# MSW_V2.net
KiCad netlist of a schematic drawn in Altium Designer
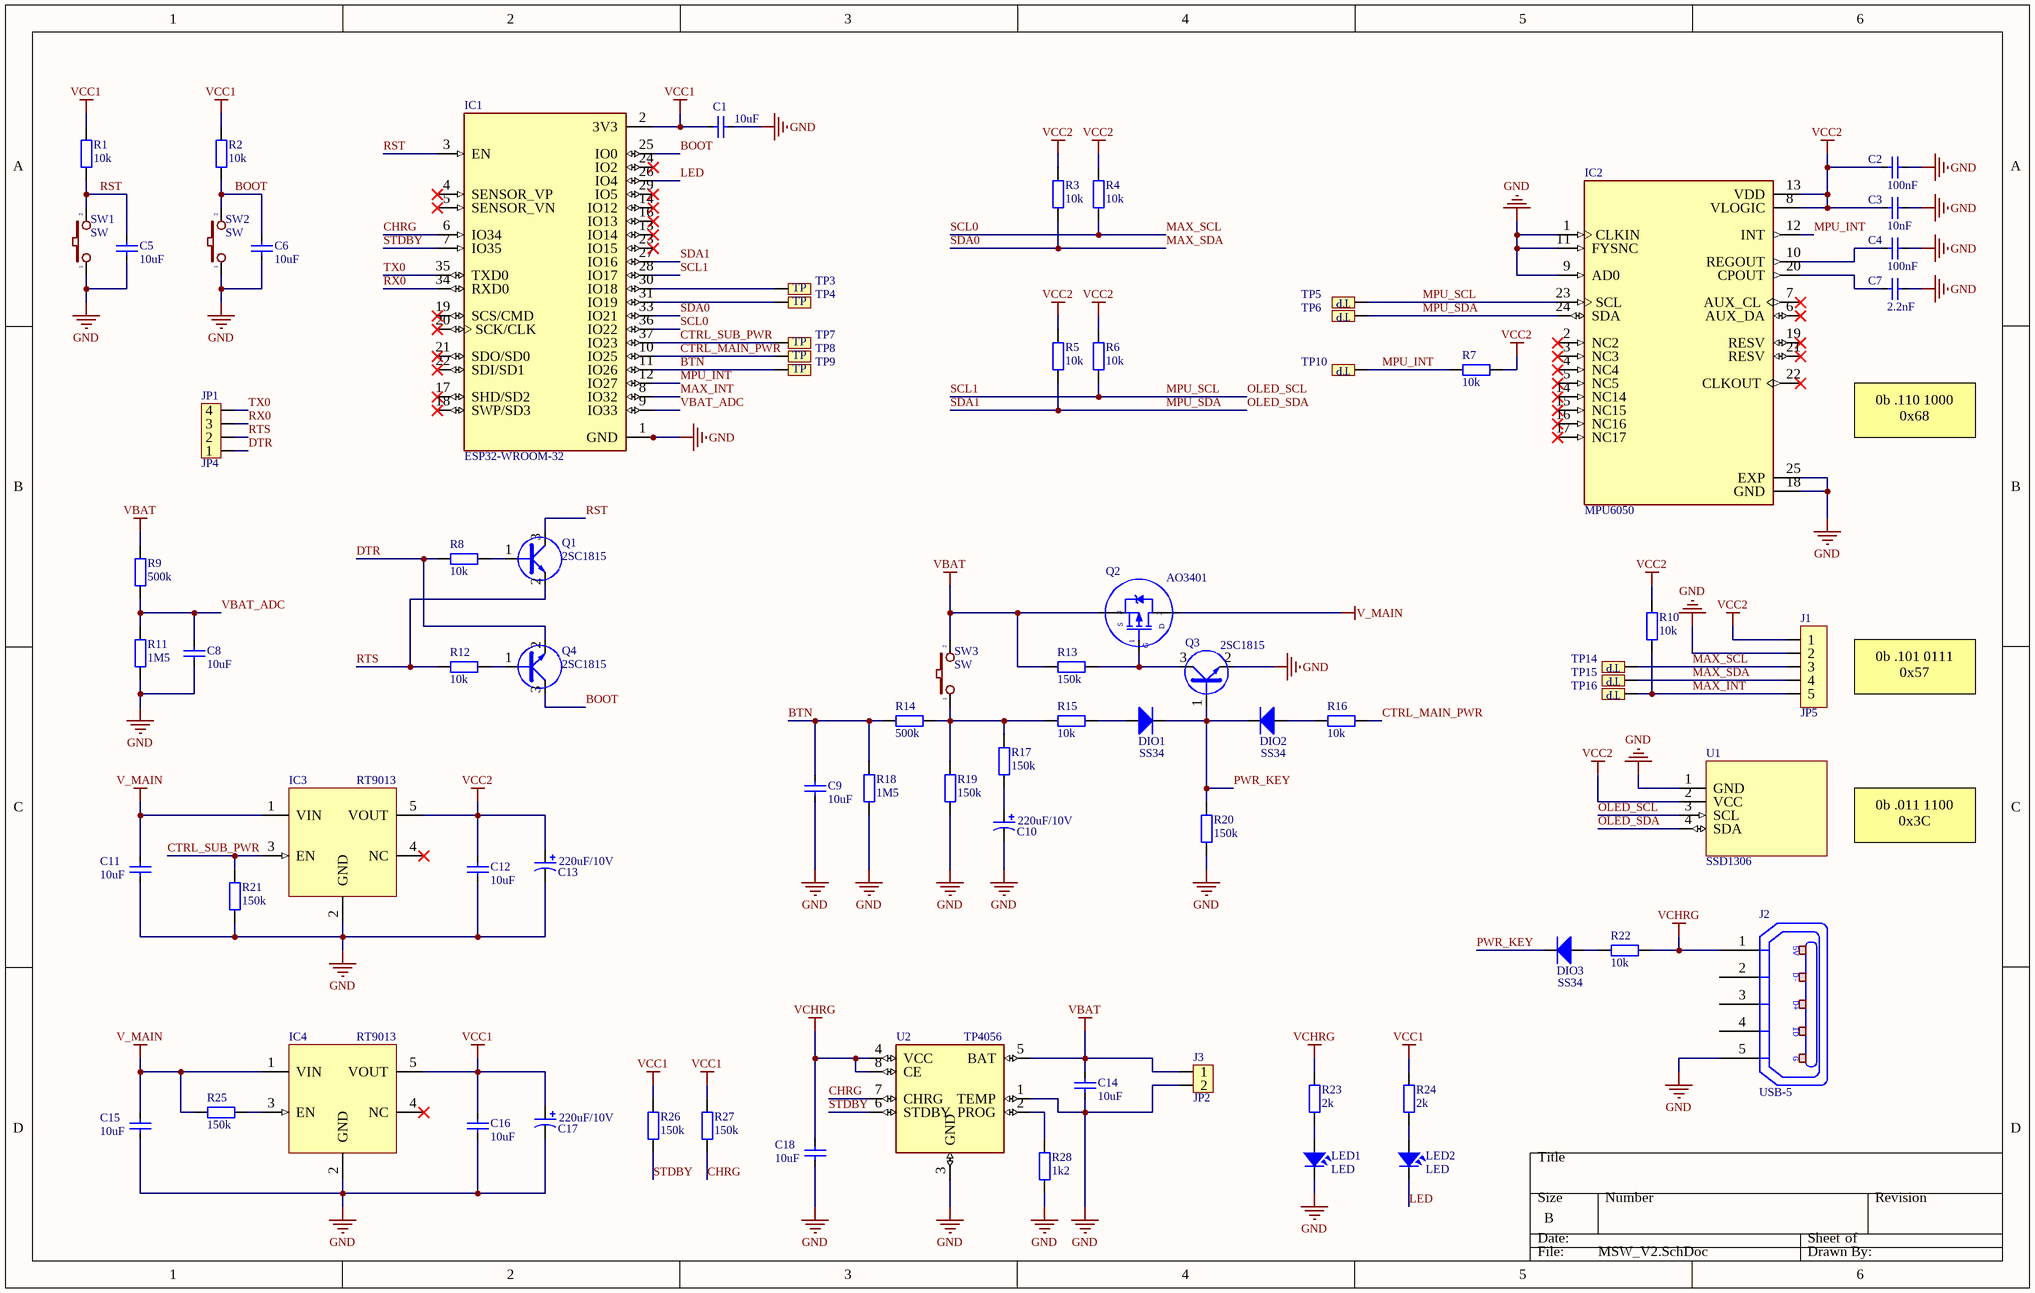
[diagram p0: MSW_V2.SchDoc]

(export (version "E")
  (design (tool "Eeschema 10.0.6"))
  (components
    (comp (ref "C1")
      (value "10uF")
      (footprint "CAP_0603")
      (description "Capacitor")
      (fields (field (name "PUBLISHER") "Altium Limited"))
      (libsource (lib "My Library") (part "CapSMD"))
    )
    (comp (ref "C2")
      (value "100nF")
      (footprint "CAP_0603")
      (description "Capacitor")
      (fields (field (name "PUBLISHER") "Altium Limited"))
      (libsource (lib "My Library") (part "CapSMD"))
    )
    (comp (ref "C3")
      (value "10nF")
      (footprint "CAP_0603")
      (description "Capacitor")
      (fields (field (name "PUBLISHER") "Altium Limited"))
      (libsource (lib "My Library") (part "CapSMD"))
    )
    (comp (ref "C4")
      (value "100nF")
      (footprint "CAP_0603")
      (description "Capacitor")
      (fields (field (name "PUBLISHER") "Altium Limited"))
      (libsource (lib "My Library") (part "CapSMD"))
    )
    (comp (ref "C5")
      (value "10uF")
      (footprint "CAP_0603")
      (description "Capacitor")
      (fields (field (name "PUBLISHER") "Altium Limited"))
      (libsource (lib "My Library") (part "CapSMD"))
    )
    (comp (ref "C6")
      (value "10uF")
      (footprint "CAP_0603")
      (description "Capacitor")
      (fields (field (name "PUBLISHER") "Altium Limited"))
      (libsource (lib "My Library") (part "CapSMD"))
    )
    (comp (ref "C7")
      (value "2.2nF")
      (footprint "CAP_0603")
      (description "Capacitor")
      (fields (field (name "PUBLISHER") "Altium Limited"))
      (libsource (lib "My Library") (part "CapSMD"))
    )
    (comp (ref "C8")
      (value "10uF")
      (footprint "CAP_0603")
      (description "Capacitor")
      (fields (field (name "PUBLISHER") "Altium Limited"))
      (libsource (lib "My Library") (part "CapSMD"))
    )
    (comp (ref "C9")
      (value "10uF")
      (footprint "CAP_0603")
      (description "Capacitor")
      (fields (field (name "PUBLISHER") "Altium Limited"))
      (libsource (lib "My Library") (part "CapSMD"))
    )
    (comp (ref "C10")
      (value "220uF/10V")
      (footprint "CAP_7343")
      (description "Polazied Tantalum Capacitor")
      (libsource (lib "My Library") (part "CAP_TAN_SMD"))
    )
    (comp (ref "C11")
      (value "10uF")
      (footprint "CAP_0603")
      (description "Capacitor")
      (fields (field (name "PUBLISHER") "Altium Limited"))
      (libsource (lib "My Library") (part "CapSMD"))
    )
    (comp (ref "C12")
      (value "10uF")
      (footprint "CAP_0603")
      (description "Capacitor")
      (fields (field (name "PUBLISHER") "Altium Limited"))
      (libsource (lib "My Library") (part "CapSMD"))
    )
    (comp (ref "C13")
      (value "220uF/10V")
      (footprint "CAP_7343")
      (description "Polazied Tantalum Capacitor")
      (libsource (lib "My Library") (part "CAP_TAN_SMD"))
    )
    (comp (ref "C14")
      (value "10uF")
      (footprint "CAP_0603")
      (description "Capacitor")
      (fields (field (name "PUBLISHER") "Altium Limited"))
      (libsource (lib "My Library") (part "CapSMD"))
    )
    (comp (ref "C15")
      (value "10uF")
      (footprint "CAP_0603")
      (description "Capacitor")
      (fields (field (name "PUBLISHER") "Altium Limited"))
      (libsource (lib "My Library") (part "CapSMD"))
    )
    (comp (ref "C16")
      (value "10uF")
      (footprint "CAP_0603")
      (description "Capacitor")
      (fields (field (name "PUBLISHER") "Altium Limited"))
      (libsource (lib "My Library") (part "CapSMD"))
    )
    (comp (ref "C17")
      (value "220uF/10V")
      (footprint "CAP_7343")
      (description "Polazied Tantalum Capacitor")
      (libsource (lib "My Library") (part "CAP_TAN_SMD"))
    )
    (comp (ref "C18")
      (value "10uF")
      (footprint "CAP_0603")
      (description "Capacitor")
      (fields (field (name "PUBLISHER") "Altium Limited"))
      (libsource (lib "My Library") (part "CapSMD"))
    )
    (comp (ref "DIO1")
      (value "SS34")
      (footprint "DIO-214AC(SMA)")
      (description "Default Diode")
      (fields (field (name "PUBLISHER") "Altium Limited"))
      (libsource (lib "My Library") (part "Diode SMD"))
    )
    (comp (ref "DIO2")
      (value "SS34")
      (footprint "DIO-214AC(SMA)")
      (description "Default Diode")
      (fields (field (name "PUBLISHER") "Altium Limited"))
      (libsource (lib "My Library") (part "Diode SMD"))
    )
    (comp (ref "DIO3")
      (value "SS34")
      (footprint "DIO-214AC(SMA)")
      (description "Default Diode")
      (fields (field (name "PUBLISHER") "Altium Limited"))
      (libsource (lib "My Library") (part "Diode SMD"))
    )
    (comp (ref "IC1")
      (value "ESP32-WROOM-32")
      (footprint "MODULE_ESP32-WROOM-32")
      (description "Bluetooth, WiFi Transceiver Module 2.4GHz ~ 2.5GHz Surface Mount")
      (fields (field (name "MF") "Espressif Systems") (field (name "DIGI-KEY_PART_NUMBER") "1904-1010-1-ND"))
      (libsource (lib "My Library") (part "ESP32-WROOM-32"))
    )
    (comp (ref "IC2")
      (value "MPU6050")
      (footprint "QFN24")
      (description "3-axis gyroscope, 3-axis accelerometer")
      (libsource (lib "My Library") (part "MPU6050_Chip"))
    )
    (comp (ref "IC3")
      (value "RT9013")
      (footprint "SOT23-5")
      (description "RT9013-33GB IC REG LINEAR 3.3V 500mA SOT23-5")
      (libsource (lib "My Library") (part "RT9013"))
    )
    (comp (ref "IC4")
      (value "RT9013")
      (footprint "SOT23-5")
      (description "RT9013-33GB IC REG LINEAR 3.3V 500mA SOT23-5")
      (libsource (lib "My Library") (part "RT9013"))
    )
    (comp (ref "J1")
      (value "JP5")
      (footprint "Header5 - TH - 1.25MM")
      (description "WR-PHD 2.54 mm Angled Socket Header")
      (fields
        (field (name "MANUFACTURER") "Würth Elektronik eiSos GmbH")
        (field (name "PARTNO") "613005143121")
        (field (name "CREATED BY") "Karrer Zheng")
      )
      (libsource (lib "My Library") (part "JP5x1"))
    )
    (comp (ref "J2")
      (value "USB-5")
      (footprint "USB-M4")
      (fields
        (field (name "MANUFACTURER") "FCI")
        (field (name "MANUFACTURER PART NUMBER") "10118193-0001LF")
        (field (name ".CREATOR") "MM")
        (field (name ".CHECKED PCB") "RF")
        (field (name ".CHECKED SCH") "MM")
      )
      (libsource (lib "My Library") (part "USB-5"))
    )
    (comp (ref "J3")
      (value "JP2")
      (footprint "JP2-C1T")
      (description "WR-PHD 2.54 mm Angled Socket Header")
      (fields
        (field (name "MANUFACTURER") "Würth Elektronik eiSos GmbH")
        (field (name "PARTNO") "613002143121")
        (field (name "CREATED BY") "Karrer Zheng")
      )
      (libsource (lib "My Library") (part "JP2"))
    )
    (comp (ref "JP1")
      (value "JP4")
      (footprint "Header4 - TH - 1.25MM")
      (description "WR-PHD 2.54 mm Angled Socket Header")
      (fields
        (field (name "MANUFACTURER") "Würth Elektronik eiSos GmbH")
        (field (name "PARTNO") "613004143121")
        (field (name "CREATED BY") "Karrer Zheng")
      )
      (libsource (lib "My Library") (part "JP4"))
    )
    (comp (ref "LED1")
      (value "LED")
      (footprint "LED-0805-Red")
      (description "LED Single colour Green and Red")
      (libsource (lib "My Library") (part "LED"))
    )
    (comp (ref "LED2")
      (value "LED")
      (footprint "LED-0805-Blue")
      (description "LED Single colour Green and Red")
      (libsource (lib "My Library") (part "LED"))
    )
    (comp (ref "Q1")
      (value "2SC1815")
      (footprint "SOT23D")
      (description "NPN 600mW, ECB")
      (libsource (lib "") (part "C1815_2"))
    )
    (comp (ref "Q2")
      (value "AO3401")
      (footprint "SOT23A")
      (description "Generic P Channel MOSFET")
      (libsource (lib "My Library") (part "MOSFET_P"))
    )
    (comp (ref "Q3")
      (value "2SC1815")
      (footprint "SOT23D")
      (description "NPN 600mW, ECB")
      (libsource (lib "My Library") (part "C1815"))
    )
    (comp (ref "Q4")
      (value "2SC1815")
      (footprint "SOT23D")
      (description "NPN 600mW, ECB")
      (libsource (lib "") (part "C1815_1"))
    )
    (comp (ref "R1")
      (value "10k")
      (footprint "RES-SMD-0603")
      (description "Resistor SMD")
      (fields
        (field (name "MANUFACTURER") "Generic Components")
        (field (name "PUBLISHER") "Altium Hobart Technology Centre")
      )
      (libsource (lib "My Library") (part "Resistor - SMD"))
    )
    (comp (ref "R2")
      (value "10k")
      (footprint "RES-SMD-0603")
      (description "Resistor SMD")
      (fields
        (field (name "MANUFACTURER") "Generic Components")
        (field (name "PUBLISHER") "Altium Hobart Technology Centre")
      )
      (libsource (lib "My Library") (part "Resistor - SMD"))
    )
    (comp (ref "R3")
      (value "10k")
      (footprint "RES-SMD-0603")
      (description "Resistor SMD")
      (fields
        (field (name "MANUFACTURER") "Generic Components")
        (field (name "PUBLISHER") "Altium Hobart Technology Centre")
      )
      (libsource (lib "My Library") (part "Resistor - SMD"))
    )
    (comp (ref "R4")
      (value "10k")
      (footprint "RES-SMD-0603")
      (description "Resistor SMD")
      (fields
        (field (name "MANUFACTURER") "Generic Components")
        (field (name "PUBLISHER") "Altium Hobart Technology Centre")
      )
      (libsource (lib "My Library") (part "Resistor - SMD"))
    )
    (comp (ref "R5")
      (value "10k")
      (footprint "RES-SMD-0603")
      (description "Resistor SMD")
      (fields
        (field (name "MANUFACTURER") "Generic Components")
        (field (name "PUBLISHER") "Altium Hobart Technology Centre")
      )
      (libsource (lib "My Library") (part "Resistor - SMD"))
    )
    (comp (ref "R6")
      (value "10k")
      (footprint "RES-SMD-0603")
      (description "Resistor SMD")
      (fields
        (field (name "MANUFACTURER") "Generic Components")
        (field (name "PUBLISHER") "Altium Hobart Technology Centre")
      )
      (libsource (lib "My Library") (part "Resistor - SMD"))
    )
    (comp (ref "R7")
      (value "10k")
      (footprint "RES-SMD-0603")
      (description "Resistor SMD")
      (fields
        (field (name "MANUFACTURER") "Generic Components")
        (field (name "PUBLISHER") "Altium Hobart Technology Centre")
      )
      (libsource (lib "My Library") (part "Resistor - SMD"))
    )
    (comp (ref "R8")
      (value "10k")
      (footprint "RES-SMD-0603")
      (description "Resistor SMD")
      (fields
        (field (name "MANUFACTURER") "Generic Components")
        (field (name "PUBLISHER") "Altium Hobart Technology Centre")
      )
      (libsource (lib "My Library") (part "Resistor - SMD"))
    )
    (comp (ref "R9")
      (value "500k")
      (footprint "RES-SMD-0603")
      (description "Resistor SMD")
      (fields
        (field (name "MANUFACTURER") "Generic Components")
        (field (name "PUBLISHER") "Altium Hobart Technology Centre")
      )
      (libsource (lib "My Library") (part "Resistor - SMD"))
    )
    (comp (ref "R10")
      (value "10k")
      (footprint "RES-SMD-0603")
      (description "Resistor SMD")
      (fields
        (field (name "MANUFACTURER") "Generic Components")
        (field (name "PUBLISHER") "Altium Hobart Technology Centre")
      )
      (libsource (lib "My Library") (part "Resistor - SMD"))
    )
    (comp (ref "R11")
      (value "1M5")
      (footprint "RES-SMD-0603")
      (description "Resistor SMD")
      (fields
        (field (name "MANUFACTURER") "Generic Components")
        (field (name "PUBLISHER") "Altium Hobart Technology Centre")
      )
      (libsource (lib "My Library") (part "Resistor - SMD"))
    )
    (comp (ref "R12")
      (value "10k")
      (footprint "RES-SMD-0603")
      (description "Resistor SMD")
      (fields
        (field (name "MANUFACTURER") "Generic Components")
        (field (name "PUBLISHER") "Altium Hobart Technology Centre")
      )
      (libsource (lib "My Library") (part "Resistor - SMD"))
    )
    (comp (ref "R13")
      (value "150k")
      (footprint "RES-SMD-0603")
      (description "Resistor SMD")
      (fields
        (field (name "MANUFACTURER") "Generic Components")
        (field (name "PUBLISHER") "Altium Hobart Technology Centre")
      )
      (libsource (lib "My Library") (part "Resistor - SMD"))
    )
    (comp (ref "R14")
      (value "500k")
      (footprint "RES-SMD-0603")
      (description "Resistor SMD")
      (fields
        (field (name "MANUFACTURER") "Generic Components")
        (field (name "PUBLISHER") "Altium Hobart Technology Centre")
      )
      (libsource (lib "My Library") (part "Resistor - SMD"))
    )
    (comp (ref "R15")
      (value "10k")
      (footprint "RES-SMD-0603")
      (description "Resistor SMD")
      (fields
        (field (name "MANUFACTURER") "Generic Components")
        (field (name "PUBLISHER") "Altium Hobart Technology Centre")
      )
      (libsource (lib "My Library") (part "Resistor - SMD"))
    )
    (comp (ref "R16")
      (value "10k")
      (footprint "RES-SMD-0603")
      (description "Resistor SMD")
      (fields
        (field (name "MANUFACTURER") "Generic Components")
        (field (name "PUBLISHER") "Altium Hobart Technology Centre")
      )
      (libsource (lib "My Library") (part "Resistor - SMD"))
    )
    (comp (ref "R17")
      (value "150k")
      (footprint "RES-SMD-0603")
      (description "Resistor SMD")
      (fields
        (field (name "MANUFACTURER") "Generic Components")
        (field (name "PUBLISHER") "Altium Hobart Technology Centre")
      )
      (libsource (lib "My Library") (part "Resistor - SMD"))
    )
    (comp (ref "R18")
      (value "1M5")
      (footprint "RES-SMD-0603")
      (description "Resistor SMD")
      (fields
        (field (name "MANUFACTURER") "Generic Components")
        (field (name "PUBLISHER") "Altium Hobart Technology Centre")
      )
      (libsource (lib "My Library") (part "Resistor - SMD"))
    )
    (comp (ref "R19")
      (value "150k")
      (footprint "RES-SMD-0603")
      (description "Resistor SMD")
      (fields
        (field (name "MANUFACTURER") "Generic Components")
        (field (name "PUBLISHER") "Altium Hobart Technology Centre")
      )
      (libsource (lib "My Library") (part "Resistor - SMD"))
    )
    (comp (ref "R20")
      (value "150k")
      (footprint "RES-SMD-0603")
      (description "Resistor SMD")
      (fields
        (field (name "MANUFACTURER") "Generic Components")
        (field (name "PUBLISHER") "Altium Hobart Technology Centre")
      )
      (libsource (lib "My Library") (part "Resistor - SMD"))
    )
    (comp (ref "R21")
      (value "150k")
      (footprint "RES-SMD-0603")
      (description "Resistor SMD")
      (fields
        (field (name "MANUFACTURER") "Generic Components")
        (field (name "PUBLISHER") "Altium Hobart Technology Centre")
      )
      (libsource (lib "My Library") (part "Resistor - SMD"))
    )
    (comp (ref "R22")
      (value "10k")
      (footprint "RES-SMD-0603")
      (description "Resistor SMD")
      (fields
        (field (name "MANUFACTURER") "Generic Components")
        (field (name "PUBLISHER") "Altium Hobart Technology Centre")
      )
      (libsource (lib "My Library") (part "Resistor - SMD"))
    )
    (comp (ref "R23")
      (value "2k")
      (footprint "RES-SMD-0603")
      (description "Resistor SMD")
      (fields
        (field (name "MANUFACTURER") "Generic Components")
        (field (name "PUBLISHER") "Altium Hobart Technology Centre")
      )
      (libsource (lib "My Library") (part "Resistor - SMD"))
    )
    (comp (ref "R24")
      (value "2k")
      (footprint "RES-SMD-0603")
      (description "Resistor SMD")
      (fields
        (field (name "MANUFACTURER") "Generic Components")
        (field (name "PUBLISHER") "Altium Hobart Technology Centre")
      )
      (libsource (lib "My Library") (part "Resistor - SMD"))
    )
    (comp (ref "R25")
      (value "150k")
      (footprint "RES-SMD-0603")
      (description "Resistor SMD")
      (fields
        (field (name "MANUFACTURER") "Generic Components")
        (field (name "PUBLISHER") "Altium Hobart Technology Centre")
      )
      (libsource (lib "My Library") (part "Resistor - SMD"))
    )
    (comp (ref "R26")
      (value "150k")
      (footprint "RES-SMD-0603")
      (description "Resistor SMD")
      (fields
        (field (name "MANUFACTURER") "Generic Components")
        (field (name "PUBLISHER") "Altium Hobart Technology Centre")
      )
      (libsource (lib "My Library") (part "Resistor - SMD"))
    )
    (comp (ref "R27")
      (value "150k")
      (footprint "RES-SMD-0603")
      (description "Resistor SMD")
      (fields
        (field (name "MANUFACTURER") "Generic Components")
        (field (name "PUBLISHER") "Altium Hobart Technology Centre")
      )
      (libsource (lib "My Library") (part "Resistor - SMD"))
    )
    (comp (ref "R28")
      (value "1k2")
      (footprint "RES-SMD-0603")
      (description "Resistor SMD")
      (fields
        (field (name "MANUFACTURER") "Generic Components")
        (field (name "PUBLISHER") "Altium Hobart Technology Centre")
      )
      (libsource (lib "My Library") (part "Resistor - SMD"))
    )
    (comp (ref "SW1")
      (value "SW")
      (footprint "SW 3x2x4")
      (description "Switch button 2 pin")
      (libsource (lib "My Library") (part "SW2"))
    )
    (comp (ref "SW2")
      (value "SW")
      (footprint "SW 3x2x4")
      (description "Switch button 2 pin")
      (libsource (lib "My Library") (part "SW2"))
    )
    (comp (ref "SW3")
      (value "SW")
      (footprint "BUTTON 2P SMD SIDE 2x4x3.5")
      (description "Switch button 2 pin")
      (libsource (lib "My Library") (part "SW2"))
    )
    (comp (ref "TP3")
      (value "TP")
      (footprint "TP_SMD")
      (description "CONNECT 1")
      (libsource (lib "My Library") (part "TP"))
    )
    (comp (ref "TP4")
      (value "TP")
      (footprint "TP_SMD")
      (description "CONNECT 1")
      (libsource (lib "My Library") (part "TP"))
    )
    (comp (ref "TP5")
      (value "TP")
      (footprint "TP_SMD")
      (description "CONNECT 1")
      (libsource (lib "") (part "TP_1"))
    )
    (comp (ref "TP6")
      (value "TP")
      (footprint "TP_SMD")
      (description "CONNECT 1")
      (libsource (lib "") (part "TP_1"))
    )
    (comp (ref "TP7")
      (value "TP")
      (footprint "TP_SMD")
      (description "CONNECT 1")
      (libsource (lib "My Library") (part "TP"))
    )
    (comp (ref "TP8")
      (value "TP")
      (footprint "TP_SMD")
      (description "CONNECT 1")
      (libsource (lib "My Library") (part "TP"))
    )
    (comp (ref "TP9")
      (value "TP")
      (footprint "TP_SMD")
      (description "CONNECT 1")
      (libsource (lib "My Library") (part "TP"))
    )
    (comp (ref "TP10")
      (value "TP")
      (footprint "TP_SMD")
      (description "CONNECT 1")
      (libsource (lib "") (part "TP_1"))
    )
    (comp (ref "TP14")
      (value "TP")
      (footprint "TP_SMD")
      (description "CONNECT 1")
      (libsource (lib "") (part "TP_1"))
    )
    (comp (ref "TP15")
      (value "TP")
      (footprint "TP_SMD")
      (description "CONNECT 1")
      (libsource (lib "") (part "TP_1"))
    )
    (comp (ref "TP16")
      (value "TP")
      (footprint "TP_SMD")
      (description "CONNECT 1")
      (libsource (lib "") (part "TP_1"))
    )
    (comp (ref "U1")
      (value "SSD1306")
      (footprint "OLED 1.3 SSD1306 NON POLE")
      (description "OLED Display 1.3\" SSD1306")
      (libsource (lib "My Library") (part "OLED 1.3 SSD1306"))
    )
    (comp (ref "U2")
      (value "TP4056")
      (footprint "TP4056")
      (description "Complete single cell Li-Ion battery with a constant current / constant voltage linear charger")
      (libsource (lib "My Library") (part "TP4056"))
    )
  )
  (nets
    (net (code "1") (name "/BOOT") (class "Default")
      (node (ref "C6") (pin "2") (pinfunction "2_2") (pintype "passive"))
      (node (ref "IC1") (pin "25") (pinfunction "IO0_25") (pintype "bidirectional"))
      (node (ref "Q4") (pin "3") (pinfunction "C_3") (pintype "passive"))
      (node (ref "R2") (pin "2") (pinfunction "2_2") (pintype "passive"))
      (node (ref "SW2") (pin "2") (pinfunction "2_2") (pintype "passive"))
    )
    (net (code "2") (name "/BTN") (class "Default")
      (node (ref "C9") (pin "2") (pinfunction "2_2") (pintype "passive"))
      (node (ref "IC1") (pin "11") (pinfunction "IO26_11") (pintype "bidirectional"))
      (node (ref "R14") (pin "2") (pinfunction "2_2") (pintype "passive"))
      (node (ref "R18") (pin "2") (pinfunction "2_2") (pintype "passive"))
      (node (ref "TP9") (pin "1") (pinfunction "0_1") (pintype "passive"))
    )
    (net (code "3") (name "/CHRG") (class "Default")
      (node (ref "IC1") (pin "6") (pinfunction "IO34_6") (pintype "input"))
      (node (ref "R27") (pin "2") (pinfunction "2_2") (pintype "passive"))
      (node (ref "U2") (pin "7") (pinfunction "CHRG_7") (pintype "bidirectional"))
    )
    (net (code "4") (name "/CTRL_MAIN_PWR") (class "Default")
      (node (ref "IC1") (pin "10") (pinfunction "IO25_10") (pintype "bidirectional"))
      (node (ref "R16") (pin "2") (pinfunction "2_2") (pintype "passive"))
      (node (ref "TP8") (pin "1") (pinfunction "0_1") (pintype "passive"))
    )
    (net (code "5") (name "/CTRL_SUB_PWR") (class "Default")
      (node (ref "IC1") (pin "37") (pinfunction "IO23_37") (pintype "bidirectional"))
      (node (ref "IC3") (pin "3") (pinfunction "EN_3") (pintype "input"))
      (node (ref "R21") (pin "1") (pinfunction "1_1") (pintype "passive"))
      (node (ref "TP7") (pin "1") (pinfunction "0_1") (pintype "passive"))
    )
    (net (code "6") (name "/DTR") (class "Default")
      (node (ref "JP1") (pin "1") (pinfunction "1_1") (pintype "passive"))
      (node (ref "Q4") (pin "2") (pinfunction "E_2") (pintype "passive"))
      (node (ref "R8") (pin "2") (pinfunction "2_2") (pintype "passive"))
    )
    (net (code "7") (name "/LED") (class "Default")
      (node (ref "IC1") (pin "26") (pinfunction "IO4_26") (pintype "bidirectional"))
      (node (ref "LED2") (pin "2") (pinfunction "2_2") (pintype "passive"))
    )
    (net (code "8") (name "/MAX_INT") (class "Default")
      (node (ref "IC1") (pin "8") (pinfunction "IO32_8") (pintype "bidirectional"))
      (node (ref "J1") (pin "5") (pinfunction "5_5") (pintype "passive"))
      (node (ref "R10") (pin "2") (pinfunction "2_2") (pintype "passive"))
      (node (ref "TP16") (pin "1") (pinfunction "0_1") (pintype "passive"))
    )
    (net (code "9") (name "/MAX_SCL") (class "Default")
      (node (ref "IC1") (pin "36") (pinfunction "IO22_36") (pintype "bidirectional"))
      (node (ref "J1") (pin "3") (pinfunction "3_3") (pintype "passive"))
      (node (ref "R4") (pin "1") (pinfunction "1_1") (pintype "passive"))
      (node (ref "TP14") (pin "1") (pinfunction "0_1") (pintype "passive"))
    )
    (net (code "10") (name "/MAX_SDA") (class "Default")
      (node (ref "IC1") (pin "33") (pinfunction "IO21_33") (pintype "bidirectional"))
      (node (ref "J1") (pin "4") (pinfunction "4_4") (pintype "passive"))
      (node (ref "R3") (pin "1") (pinfunction "1_1") (pintype "passive"))
      (node (ref "TP15") (pin "1") (pinfunction "0_1") (pintype "passive"))
    )
    (net (code "11") (name "/MPU_INT") (class "Default")
      (node (ref "IC1") (pin "12") (pinfunction "IO27_12") (pintype "bidirectional"))
      (node (ref "IC2") (pin "12") (pinfunction "INT_12") (pintype "output"))
      (node (ref "R7") (pin "2") (pinfunction "2_2") (pintype "passive"))
      (node (ref "TP10") (pin "1") (pinfunction "0_1") (pintype "passive"))
    )
    (net (code "12") (name "/MPU_SCL") (class "Default")
      (node (ref "IC1") (pin "28") (pinfunction "IO17_28") (pintype "bidirectional"))
      (node (ref "IC2") (pin "23") (pinfunction "SCL_23") (pintype "input"))
      (node (ref "R6") (pin "1") (pinfunction "1_1") (pintype "passive"))
      (node (ref "TP5") (pin "1") (pinfunction "0_1") (pintype "passive"))
      (node (ref "U1") (pin "3") (pinfunction "SCL_3") (pintype "input"))
    )
    (net (code "13") (name "/MPU_SDA") (class "Default")
      (node (ref "IC1") (pin "27") (pinfunction "IO16_27") (pintype "bidirectional"))
      (node (ref "IC2") (pin "24") (pinfunction "SDA_24") (pintype "bidirectional"))
      (node (ref "R5") (pin "1") (pinfunction "1_1") (pintype "passive"))
      (node (ref "TP6") (pin "1") (pinfunction "0_1") (pintype "passive"))
      (node (ref "U1") (pin "4") (pinfunction "SDA_4") (pintype "bidirectional"))
    )
    (net (code "14") (name "/PWR_KEY") (class "Default")
      (node (ref "DIO1") (pin "2") (pinfunction "K_2") (pintype "passive"))
      (node (ref "DIO2") (pin "2") (pinfunction "K_2") (pintype "passive"))
      (node (ref "DIO3") (pin "2") (pinfunction "K_2") (pintype "passive"))
      (node (ref "Q3") (pin "1") (pinfunction "B_1") (pintype "passive"))
      (node (ref "R20") (pin "1") (pinfunction "1_1") (pintype "passive"))
    )
    (net (code "15") (name "/RST") (class "Default")
      (node (ref "C5") (pin "2") (pinfunction "2_2") (pintype "passive"))
      (node (ref "IC1") (pin "3") (pinfunction "EN_3") (pintype "input"))
      (node (ref "Q1") (pin "3") (pinfunction "C_3") (pintype "passive"))
      (node (ref "R1") (pin "2") (pinfunction "2_2") (pintype "passive"))
      (node (ref "SW1") (pin "2") (pinfunction "2_2") (pintype "passive"))
    )
    (net (code "16") (name "/RTS") (class "Default")
      (node (ref "JP1") (pin "2") (pinfunction "2_2") (pintype "passive"))
      (node (ref "Q1") (pin "2") (pinfunction "E_2") (pintype "passive"))
      (node (ref "R12") (pin "2") (pinfunction "2_2") (pintype "passive"))
    )
    (net (code "17") (name "/RX0") (class "Default")
      (node (ref "IC1") (pin "34") (pinfunction "RXD0_34") (pintype "bidirectional"))
      (node (ref "JP1") (pin "3") (pinfunction "3_3") (pintype "passive"))
    )
    (net (code "18") (name "/STDBY") (class "Default")
      (node (ref "IC1") (pin "7") (pinfunction "IO35_7") (pintype "input"))
      (node (ref "R26") (pin "2") (pinfunction "2_2") (pintype "passive"))
      (node (ref "U2") (pin "6") (pinfunction "STDBY_6") (pintype "bidirectional"))
    )
    (net (code "19") (name "/TX0") (class "Default")
      (node (ref "IC1") (pin "35") (pinfunction "TXD0_35") (pintype "bidirectional"))
      (node (ref "JP1") (pin "4") (pinfunction "4_4") (pintype "passive"))
    )
    (net (code "20") (name "/VBAT_ADC") (class "Default")
      (node (ref "C8") (pin "2") (pinfunction "2_2") (pintype "passive"))
      (node (ref "IC1") (pin "9") (pinfunction "IO33_9") (pintype "bidirectional"))
      (node (ref "R11") (pin "2") (pinfunction "2_2") (pintype "passive"))
      (node (ref "R9") (pin "1") (pinfunction "1_1") (pintype "passive"))
    )
    (net (code "21") (name "GND") (class "Default")
      (node (ref "C1") (pin "1") (pinfunction "1_1") (pintype "passive"))
      (node (ref "C10") (pin "2") (pinfunction "2_2") (pintype "passive"))
      (node (ref "C11") (pin "1") (pinfunction "1_1") (pintype "passive"))
      (node (ref "C12") (pin "1") (pinfunction "1_1") (pintype "passive"))
      (node (ref "C13") (pin "2") (pinfunction "2_2") (pintype "passive"))
      (node (ref "C14") (pin "1") (pinfunction "1_1") (pintype "passive"))
      (node (ref "C15") (pin "1") (pinfunction "1_1") (pintype "passive"))
      (node (ref "C16") (pin "1") (pinfunction "1_1") (pintype "passive"))
      (node (ref "C17") (pin "2") (pinfunction "2_2") (pintype "passive"))
      (node (ref "C18") (pin "1") (pinfunction "1_1") (pintype "passive"))
      (node (ref "C2") (pin "1") (pinfunction "1_1") (pintype "passive"))
      (node (ref "C3") (pin "1") (pinfunction "1_1") (pintype "passive"))
      (node (ref "C4") (pin "1") (pinfunction "1_1") (pintype "passive"))
      (node (ref "C5") (pin "1") (pinfunction "1_1") (pintype "passive"))
      (node (ref "C6") (pin "1") (pinfunction "1_1") (pintype "passive"))
      (node (ref "C7") (pin "1") (pinfunction "1_1") (pintype "passive"))
      (node (ref "C8") (pin "1") (pinfunction "1_1") (pintype "passive"))
      (node (ref "C9") (pin "1") (pinfunction "1_1") (pintype "passive"))
      (node (ref "IC1") (pin "1") (pinfunction "GND_1") (pintype "power_in"))
      (node (ref "IC1") (pin "15") (pinfunction "GND_15") (pintype "power_in"))
      (node (ref "IC1") (pin "38") (pinfunction "GND_38") (pintype "power_in"))
      (node (ref "IC1") (pin "39_1") (pinfunction "GND_39_1") (pintype "power_in"))
      (node (ref "IC1") (pin "39_10") (pinfunction "GND_39_10") (pintype "power_in"))
      (node (ref "IC1") (pin "39_11") (pinfunction "GND_39_11") (pintype "power_in"))
      (node (ref "IC1") (pin "39_12") (pinfunction "GND_39_12") (pintype "power_in"))
      (node (ref "IC1") (pin "39_13") (pinfunction "GND_39_13") (pintype "power_in"))
      (node (ref "IC1") (pin "39_14") (pinfunction "GND_39_14") (pintype "power_in"))
      (node (ref "IC1") (pin "39_15") (pinfunction "GND_39_15") (pintype "power_in"))
      (node (ref "IC1") (pin "39_16") (pinfunction "GND_39_16") (pintype "power_in"))
      (node (ref "IC1") (pin "39_17") (pinfunction "GND_39_17") (pintype "power_in"))
      (node (ref "IC1") (pin "39_18") (pinfunction "GND_39_18") (pintype "power_in"))
      (node (ref "IC1") (pin "39_19") (pinfunction "GND_39_19") (pintype "power_in"))
      (node (ref "IC1") (pin "39_2") (pinfunction "GND_39_2") (pintype "power_in"))
      (node (ref "IC1") (pin "39_20") (pinfunction "GND_39_20") (pintype "power_in"))
      (node (ref "IC1") (pin "39_21") (pinfunction "GND_39_21") (pintype "power_in"))
      (node (ref "IC1") (pin "39_3") (pinfunction "GND_39_3") (pintype "power_in"))
      (node (ref "IC1") (pin "39_4") (pinfunction "GND_39_4") (pintype "power_in"))
      (node (ref "IC1") (pin "39_5") (pinfunction "GND_39_5") (pintype "power_in"))
      (node (ref "IC1") (pin "39_6") (pinfunction "GND_39_6") (pintype "power_in"))
      (node (ref "IC1") (pin "39_7") (pinfunction "GND_39_7") (pintype "power_in"))
      (node (ref "IC1") (pin "39_8") (pinfunction "GND_39_8") (pintype "power_in"))
      (node (ref "IC1") (pin "39_9") (pinfunction "GND_39_9") (pintype "power_in"))
      (node (ref "IC2") (pin "1") (pinfunction "CLKIN_1") (pintype "input"))
      (node (ref "IC2") (pin "11") (pinfunction "FYSNC_11") (pintype "input"))
      (node (ref "IC2") (pin "18") (pinfunction "GND_18") (pintype "power_in"))
      (node (ref "IC2") (pin "25") (pinfunction "EXP_25") (pintype "power_in"))
      (node (ref "IC2") (pin "9") (pinfunction "AD0_9") (pintype "input"))
      (node (ref "IC3") (pin "2") (pinfunction "GND_2") (pintype "power_in"))
      (node (ref "IC4") (pin "2") (pinfunction "GND_2") (pintype "power_in"))
      (node (ref "J1") (pin "2") (pinfunction "2_2") (pintype "passive"))
      (node (ref "J2") (pin "5") (pinfunction "P5_5") (pintype "passive"))
      (node (ref "J3") (pin "2") (pinfunction "2_2") (pintype "passive"))
      (node (ref "LED1") (pin "2") (pinfunction "2_2") (pintype "passive"))
      (node (ref "Q3") (pin "2") (pinfunction "E_2") (pintype "passive"))
      (node (ref "R11") (pin "1") (pinfunction "1_1") (pintype "passive"))
      (node (ref "R18") (pin "1") (pinfunction "1_1") (pintype "passive"))
      (node (ref "R19") (pin "2") (pinfunction "2_2") (pintype "passive"))
      (node (ref "R20") (pin "2") (pinfunction "2_2") (pintype "passive"))
      (node (ref "R21") (pin "2") (pinfunction "2_2") (pintype "passive"))
      (node (ref "R28") (pin "1") (pinfunction "1_1") (pintype "passive"))
      (node (ref "SW1") (pin "1") (pinfunction "1_1") (pintype "passive"))
      (node (ref "SW2") (pin "1") (pinfunction "1_1") (pintype "passive"))
      (node (ref "U1") (pin "1") (pinfunction "GND_1") (pintype "power_in"))
      (node (ref "U2") (pin "1") (pinfunction "TEMP_1") (pintype "bidirectional"))
      (node (ref "U2") (pin "3") (pinfunction "GND_3") (pintype "bidirectional"))
    )
    (net (code "22") (name "Net-(C10-Pad1)") (class "Default")
      (node (ref "C10") (pin "1") (pinfunction "1_1") (pintype "passive"))
      (node (ref "R17") (pin "2") (pinfunction "2_2") (pintype "passive"))
    )
    (net (code "23") (name "Net-(DIO1-A)") (class "Default")
      (node (ref "DIO1") (pin "1") (pinfunction "A_1") (pintype "passive"))
      (node (ref "R15") (pin "2") (pinfunction "2_2") (pintype "passive"))
    )
    (net (code "24") (name "Net-(DIO2-A)") (class "Default")
      (node (ref "DIO2") (pin "1") (pinfunction "A_1") (pintype "passive"))
      (node (ref "R16") (pin "1") (pinfunction "1_1") (pintype "passive"))
    )
    (net (code "25") (name "Net-(DIO3-A)") (class "Default")
      (node (ref "DIO3") (pin "1") (pinfunction "A_1") (pintype "passive"))
      (node (ref "R22") (pin "1") (pinfunction "1_1") (pintype "passive"))
    )
    (net (code "26") (name "Net-(IC1-IO18)") (class "Default")
      (node (ref "IC1") (pin "30") (pinfunction "IO18_30") (pintype "bidirectional"))
      (node (ref "TP3") (pin "1") (pinfunction "0_1") (pintype "passive"))
    )
    (net (code "27") (name "Net-(IC1-IO19)") (class "Default")
      (node (ref "IC1") (pin "31") (pinfunction "IO19_31") (pintype "bidirectional"))
      (node (ref "TP4") (pin "1") (pinfunction "0_1") (pintype "passive"))
    )
    (net (code "28") (name "Net-(IC2-CPOUT)") (class "Default")
      (node (ref "C7") (pin "2") (pinfunction "2_2") (pintype "passive"))
      (node (ref "IC2") (pin "20") (pinfunction "CPOUT_20") (pintype "output"))
    )
    (net (code "29") (name "Net-(IC2-REGOUT)") (class "Default")
      (node (ref "C4") (pin "2") (pinfunction "2_2") (pintype "passive"))
      (node (ref "IC2") (pin "10") (pinfunction "REGOUT_10") (pintype "output"))
    )
    (net (code "30") (name "Net-(IC4-EN)") (class "Default")
      (node (ref "IC4") (pin "3") (pinfunction "EN_3") (pintype "input"))
      (node (ref "R25") (pin "2") (pinfunction "2_2") (pintype "passive"))
    )
    (net (code "31") (name "Net-(LED1-Pad1)") (class "Default")
      (node (ref "LED1") (pin "1") (pinfunction "1_1") (pintype "passive"))
      (node (ref "R23") (pin "1") (pinfunction "1_1") (pintype "passive"))
    )
    (net (code "32") (name "Net-(LED2-Pad1)") (class "Default")
      (node (ref "LED2") (pin "1") (pinfunction "1_1") (pintype "passive"))
      (node (ref "R24") (pin "1") (pinfunction "1_1") (pintype "passive"))
    )
    (net (code "33") (name "Net-(Q1-B)") (class "Default")
      (node (ref "Q1") (pin "1") (pinfunction "B_1") (pintype "passive"))
      (node (ref "R8") (pin "1") (pinfunction "1_1") (pintype "passive"))
    )
    (net (code "34") (name "Net-(Q2-G)") (class "Default")
      (node (ref "Q2") (pin "1") (pinfunction "G_1") (pintype "passive"))
      (node (ref "Q3") (pin "3") (pinfunction "C_3") (pintype "passive"))
      (node (ref "R13") (pin "2") (pinfunction "2_2") (pintype "passive"))
    )
    (net (code "35") (name "Net-(Q4-B)") (class "Default")
      (node (ref "Q4") (pin "1") (pinfunction "B_1") (pintype "passive"))
      (node (ref "R12") (pin "1") (pinfunction "1_1") (pintype "passive"))
    )
    (net (code "36") (name "Net-(R14-Pad1)") (class "Default")
      (node (ref "R14") (pin "1") (pinfunction "1_1") (pintype "passive"))
      (node (ref "R15") (pin "1") (pinfunction "1_1") (pintype "passive"))
      (node (ref "R17") (pin "1") (pinfunction "1_1") (pintype "passive"))
      (node (ref "R19") (pin "1") (pinfunction "1_1") (pintype "passive"))
      (node (ref "SW3") (pin "1") (pinfunction "1_1") (pintype "passive"))
    )
    (net (code "37") (name "Net-(U2-PROG)") (class "Default")
      (node (ref "R28") (pin "2") (pinfunction "2_2") (pintype "passive"))
      (node (ref "U2") (pin "2") (pinfunction "PROG_2") (pintype "bidirectional"))
    )
    (net (code "38") (name "VBAT") (class "Default")
      (node (ref "C14") (pin "2") (pinfunction "2_2") (pintype "passive"))
      (node (ref "J3") (pin "1") (pinfunction "1_1") (pintype "passive"))
      (node (ref "Q2") (pin "3") (pinfunction "S_3") (pintype "passive"))
      (node (ref "R13") (pin "1") (pinfunction "1_1") (pintype "passive"))
      (node (ref "R9") (pin "2") (pinfunction "2_2") (pintype "passive"))
      (node (ref "SW3") (pin "2") (pinfunction "2_2") (pintype "passive"))
      (node (ref "U2") (pin "5") (pinfunction "BAT_5") (pintype "bidirectional"))
    )
    (net (code "39") (name "VCC1") (class "Default")
      (node (ref "C1") (pin "2") (pinfunction "2_2") (pintype "passive"))
      (node (ref "C16") (pin "2") (pinfunction "2_2") (pintype "passive"))
      (node (ref "C17") (pin "1") (pinfunction "1_1") (pintype "passive"))
      (node (ref "IC1") (pin "2") (pinfunction "3V3_2") (pintype "power_in"))
      (node (ref "IC4") (pin "5") (pinfunction "VOUT_5") (pintype "power_in"))
      (node (ref "R1") (pin "1") (pinfunction "1_1") (pintype "passive"))
      (node (ref "R2") (pin "1") (pinfunction "1_1") (pintype "passive"))
      (node (ref "R24") (pin "2") (pinfunction "2_2") (pintype "passive"))
      (node (ref "R26") (pin "1") (pinfunction "1_1") (pintype "passive"))
      (node (ref "R27") (pin "1") (pinfunction "1_1") (pintype "passive"))
    )
    (net (code "40") (name "VCC2") (class "Default")
      (node (ref "C12") (pin "2") (pinfunction "2_2") (pintype "passive"))
      (node (ref "C13") (pin "1") (pinfunction "1_1") (pintype "passive"))
      (node (ref "C2") (pin "2") (pinfunction "2_2") (pintype "passive"))
      (node (ref "C3") (pin "2") (pinfunction "2_2") (pintype "passive"))
      (node (ref "IC2") (pin "13") (pinfunction "VDD_13") (pintype "power_in"))
      (node (ref "IC2") (pin "8") (pinfunction "VLOGIC_8") (pintype "power_in"))
      (node (ref "IC3") (pin "5") (pinfunction "VOUT_5") (pintype "power_in"))
      (node (ref "J1") (pin "1") (pinfunction "1_1") (pintype "passive"))
      (node (ref "R10") (pin "1") (pinfunction "1_1") (pintype "passive"))
      (node (ref "R3") (pin "2") (pinfunction "2_2") (pintype "passive"))
      (node (ref "R4") (pin "2") (pinfunction "2_2") (pintype "passive"))
      (node (ref "R5") (pin "2") (pinfunction "2_2") (pintype "passive"))
      (node (ref "R6") (pin "2") (pinfunction "2_2") (pintype "passive"))
      (node (ref "R7") (pin "1") (pinfunction "1_1") (pintype "passive"))
      (node (ref "U1") (pin "2") (pinfunction "VCC_2") (pintype "power_in"))
    )
    (net (code "41") (name "VCHRG") (class "Default")
      (node (ref "C18") (pin "2") (pinfunction "2_2") (pintype "passive"))
      (node (ref "J2") (pin "1") (pinfunction "P1_1") (pintype "passive"))
      (node (ref "R22") (pin "2") (pinfunction "2_2") (pintype "passive"))
      (node (ref "R23") (pin "2") (pinfunction "2_2") (pintype "passive"))
      (node (ref "U2") (pin "4") (pinfunction "VCC_4") (pintype "bidirectional"))
      (node (ref "U2") (pin "8") (pinfunction "CE_8") (pintype "bidirectional"))
    )
    (net (code "42") (name "V_MAIN") (class "Default")
      (node (ref "C11") (pin "2") (pinfunction "2_2") (pintype "passive"))
      (node (ref "C15") (pin "2") (pinfunction "2_2") (pintype "passive"))
      (node (ref "IC3") (pin "1") (pinfunction "VIN_1") (pintype "power_in"))
      (node (ref "IC4") (pin "1") (pinfunction "VIN_1") (pintype "power_in"))
      (node (ref "Q2") (pin "2") (pinfunction "D_2") (pintype "passive"))
      (node (ref "R25") (pin "1") (pinfunction "1_1") (pintype "passive"))
    )
    (net (code "43") (name "unconnected-(IC1-IO2-Pad24)") (class "Default")
      (node (ref "IC1") (pin "24") (pinfunction "IO2_24") (pintype "bidirectional+no_connect"))
    )
    (net (code "44") (name "unconnected-(IC1-IO5-Pad29)") (class "Default")
      (node (ref "IC1") (pin "29") (pinfunction "IO5_29") (pintype "bidirectional+no_connect"))
    )
    (net (code "45") (name "unconnected-(IC1-IO12-Pad14)") (class "Default")
      (node (ref "IC1") (pin "14") (pinfunction "IO12_14") (pintype "bidirectional+no_connect"))
    )
    (net (code "46") (name "unconnected-(IC1-IO13-Pad16)") (class "Default")
      (node (ref "IC1") (pin "16") (pinfunction "IO13_16") (pintype "bidirectional+no_connect"))
    )
    (net (code "47") (name "unconnected-(IC1-IO14-Pad13)") (class "Default")
      (node (ref "IC1") (pin "13") (pinfunction "IO14_13") (pintype "bidirectional+no_connect"))
    )
    (net (code "48") (name "unconnected-(IC1-IO15-Pad23)") (class "Default")
      (node (ref "IC1") (pin "23") (pinfunction "IO15_23") (pintype "bidirectional+no_connect"))
    )
    (net (code "49") (name "unconnected-(IC1-SCK{slash}CLK-Pad20)") (class "Default")
      (node (ref "IC1") (pin "20") (pinfunction "SCK/CLK_20") (pintype "bidirectional+no_connect"))
    )
    (net (code "50") (name "unconnected-(IC1-SCS{slash}CMD-Pad19)") (class "Default")
      (node (ref "IC1") (pin "19") (pinfunction "SCS/CMD_19") (pintype "bidirectional+no_connect"))
    )
    (net (code "51") (name "unconnected-(IC1-SDI{slash}SD1-Pad22)") (class "Default")
      (node (ref "IC1") (pin "22") (pinfunction "SDI/SD1_22") (pintype "bidirectional+no_connect"))
    )
    (net (code "52") (name "unconnected-(IC1-SDO{slash}SD0-Pad21)") (class "Default")
      (node (ref "IC1") (pin "21") (pinfunction "SDO/SD0_21") (pintype "bidirectional+no_connect"))
    )
    (net (code "53") (name "unconnected-(IC1-SENSOR_VN-Pad5)") (class "Default")
      (node (ref "IC1") (pin "5") (pinfunction "SENSOR_VN_5") (pintype "input+no_connect"))
    )
    (net (code "54") (name "unconnected-(IC1-SENSOR_VP-Pad4)") (class "Default")
      (node (ref "IC1") (pin "4") (pinfunction "SENSOR_VP_4") (pintype "input+no_connect"))
    )
    (net (code "55") (name "unconnected-(IC1-SHD{slash}SD2-Pad17)") (class "Default")
      (node (ref "IC1") (pin "17") (pinfunction "SHD/SD2_17") (pintype "bidirectional+no_connect"))
    )
    (net (code "56") (name "unconnected-(IC1-SWP{slash}SD3-Pad18)") (class "Default")
      (node (ref "IC1") (pin "18") (pinfunction "SWP/SD3_18") (pintype "bidirectional+no_connect"))
    )
    (net (code "57") (name "unconnected-(IC2-AUX_CL-Pad7)") (class "Default")
      (node (ref "IC2") (pin "7") (pinfunction "AUX_CL_7") (pintype "output+no_connect"))
    )
    (net (code "58") (name "unconnected-(IC2-AUX_DA-Pad6)") (class "Default")
      (node (ref "IC2") (pin "6") (pinfunction "AUX_DA_6") (pintype "bidirectional+no_connect"))
    )
    (net (code "59") (name "unconnected-(IC2-CLKOUT-Pad22)") (class "Default")
      (node (ref "IC2") (pin "22") (pinfunction "CLKOUT_22") (pintype "output+no_connect"))
    )
    (net (code "60") (name "unconnected-(IC2-NC2-Pad2)") (class "Default")
      (node (ref "IC2") (pin "2") (pinfunction "NC2_2") (pintype "input+no_connect"))
    )
    (net (code "61") (name "unconnected-(IC2-NC3-Pad3)") (class "Default")
      (node (ref "IC2") (pin "3") (pinfunction "NC3_3") (pintype "input+no_connect"))
    )
    (net (code "62") (name "unconnected-(IC2-NC4-Pad4)") (class "Default")
      (node (ref "IC2") (pin "4") (pinfunction "NC4_4") (pintype "input+no_connect"))
    )
    (net (code "63") (name "unconnected-(IC2-NC5-Pad5)") (class "Default")
      (node (ref "IC2") (pin "5") (pinfunction "NC5_5") (pintype "input+no_connect"))
    )
    (net (code "64") (name "unconnected-(IC2-NC14-Pad14)") (class "Default")
      (node (ref "IC2") (pin "14") (pinfunction "NC14_14") (pintype "input+no_connect"))
    )
    (net (code "65") (name "unconnected-(IC2-NC15-Pad15)") (class "Default")
      (node (ref "IC2") (pin "15") (pinfunction "NC15_15") (pintype "input+no_connect"))
    )
    (net (code "66") (name "unconnected-(IC2-NC16-Pad16)") (class "Default")
      (node (ref "IC2") (pin "16") (pinfunction "NC16_16") (pintype "input+no_connect"))
    )
    (net (code "67") (name "unconnected-(IC2-NC17-Pad17)") (class "Default")
      (node (ref "IC2") (pin "17") (pinfunction "NC17_17") (pintype "input+no_connect"))
    )
    (net (code "68") (name "unconnected-(IC2-RESV-Pad19)") (class "Default")
      (node (ref "IC2") (pin "19") (pinfunction "RESV_19") (pintype "bidirectional+no_connect"))
    )
    (net (code "69") (name "unconnected-(IC2-RESV-Pad21)") (class "Default")
      (node (ref "IC2") (pin "21") (pinfunction "RESV_21") (pintype "bidirectional+no_connect"))
    )
    (net (code "70") (name "unconnected-(IC3-NC-Pad4)") (class "Default")
      (node (ref "IC3") (pin "4") (pinfunction "NC_4") (pintype "passive+no_connect"))
    )
    (net (code "71") (name "unconnected-(IC4-NC-Pad4)") (class "Default")
      (node (ref "IC4") (pin "4") (pinfunction "NC_4") (pintype "passive+no_connect"))
    )
    (net (code "72") (name "unconnected-(J2-P2-Pad2)") (class "Default")
      (node (ref "J2") (pin "2") (pinfunction "P2_2") (pintype "passive"))
    )
    (net (code "73") (name "unconnected-(J2-P3-Pad3)") (class "Default")
      (node (ref "J2") (pin "3") (pinfunction "P3_3") (pintype "passive"))
    )
    (net (code "74") (name "unconnected-(J2-P4-Pad4)") (class "Default")
      (node (ref "J2") (pin "4") (pinfunction "P4_4") (pintype "passive"))
    )
  )
)
